# SCH_Carrier-Board_2026-08-28.net
KiCad netlist of a schematic drawn in EasyEDA
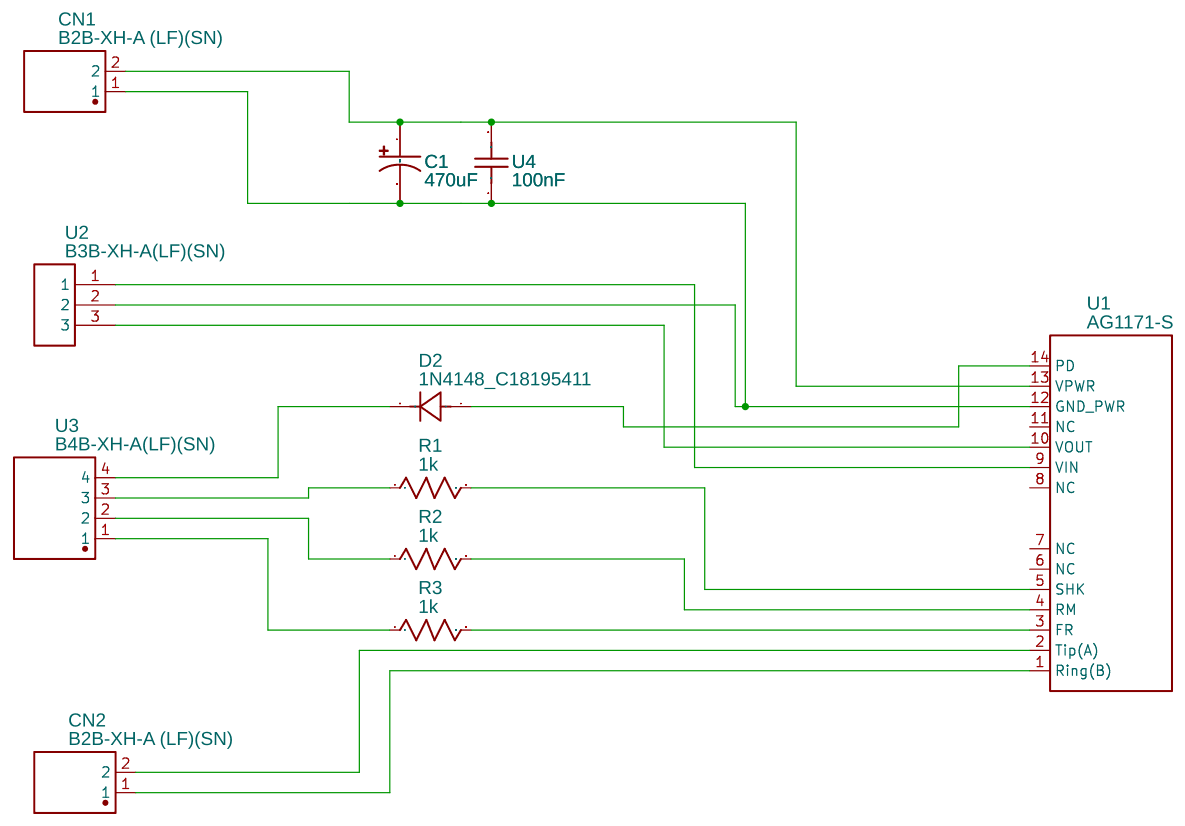
[diagram p0: schematic sheet]

(export (version "E")
  (design (tool "Eeschema 10.0.6"))
  (components
    (comp (ref "C1")
      (value "470uF")
      (fields (field (name "Manufacturer Part") "UPW1C471MPD") (field (name "Manufacturer") "Nichicon(尼吉康)"))
      (libsource (lib "") (part "UPW1C471MPD"))
    )
    (comp (ref "CN1")
      (value "B2B-XH-A (LF)(SN)")
      (fields (field (name "Manufacturer Part") "B2B-XH-A(LF)(SN)") (field (name "Manufacturer") "JST"))
      (libsource (lib "") (part "B2B-XH-A (LF)(SN)"))
    )
    (comp (ref "CN2")
      (value "B2B-XH-A (LF)(SN)")
      (fields (field (name "Manufacturer Part") "B2B-XH-A(LF)(SN)") (field (name "Manufacturer") "JST"))
      (libsource (lib "") (part "B2B-XH-A (LF)(SN)"))
    )
    (comp (ref "D2")
      (value "1N4148_C18195411")
      (fields (field (name "Manufacturer Part") "1N4148") (field (name "Manufacturer") "LJ(朗捷)"))
      (libsource (lib "") (part "1N4148_C18195411"))
    )
    (comp (ref "R1") (value "1k") (libsource (lib "") (part "R_0603_US")))
    (comp (ref "R2") (value "1k") (libsource (lib "") (part "R_0603_US")))
    (comp (ref "R3") (value "1k") (libsource (lib "") (part "R_0603_US")))
    (comp (ref "U1")
      (value "AG1171-S")
      (fields (field (name "Manufacturer") "Silvertel"))
      (libsource (lib "") (part "AG1171-S"))
    )
    (comp (ref "U2")
      (value "B3B-XH-A(LF)(SN)")
      (fields (field (name "Manufacturer") "JST"))
      (libsource (lib "") (part "B3B-XH-A(LF)(SN)"))
    )
    (comp (ref "U3")
      (value "B4B-XH-A(LF)(SN)")
      (fields (field (name "Manufacturer") "JST"))
      (libsource (lib "") (part "B4B-XH-A(LF)(SN)"))
    )
    (comp (ref "U4")
      (value "100nF")
      (fields (field (name "Manufacturer Part") "K104K10X7RF5UH5") (field (name "Manufacturer") "VISHAY(威世)"))
      (libsource (lib "") (part "K104K10X7RF5UH5"))
    )
  )
  (nets
    (net (code "1") (name "Net-(D2-A)") (class "Default")
      (node (ref "D2") (pin "1") (pinfunction "A_1") (pintype "unspecified"))
      (node (ref "U1") (pin "14") (pinfunction "PD_14") (pintype "unspecified"))
    )
    (net (code "2") (name "Net-(D2-C)") (class "Default")
      (node (ref "D2") (pin "2") (pinfunction "C_2") (pintype "unspecified"))
      (node (ref "U3") (pin "4") (pinfunction "4_4") (pintype "unspecified"))
    )
    (net (code "3") (name "Net-(R1-Pad1)") (class "Default")
      (node (ref "R1") (pin "1") (pinfunction "1_1") (pintype "unspecified"))
      (node (ref "U3") (pin "3") (pinfunction "3_3") (pintype "unspecified"))
    )
    (net (code "4") (name "Net-(R2-Pad1)") (class "Default")
      (node (ref "R2") (pin "1") (pinfunction "1_1") (pintype "unspecified"))
      (node (ref "U3") (pin "2") (pinfunction "2_2") (pintype "unspecified"))
    )
    (net (code "5") (name "Net-(R3-Pad1)") (class "Default")
      (node (ref "R3") (pin "1") (pinfunction "1_1") (pintype "unspecified"))
      (node (ref "U3") (pin "1") (pinfunction "1_1") (pintype "unspecified"))
    )
    (net (code "6") (name "Net-(U1-FR)") (class "Default")
      (node (ref "R3") (pin "2") (pinfunction "2_2") (pintype "unspecified"))
      (node (ref "U1") (pin "3") (pinfunction "FR_3") (pintype "unspecified"))
    )
    (net (code "7") (name "Net-(U1-GND_PWR)") (class "Default")
      (node (ref "C1") (pin "2") (pinfunction "2_2") (pintype "unspecified"))
      (node (ref "CN1") (pin "1") (pinfunction "1_1") (pintype "unspecified"))
      (node (ref "U1") (pin "12") (pinfunction "GND_PWR_12") (pintype "unspecified"))
      (node (ref "U2") (pin "2") (pinfunction "2_2") (pintype "unspecified"))
      (node (ref "U4") (pin "1") (pinfunction "1_1") (pintype "unspecified"))
    )
    (net (code "8") (name "Net-(U1-RM)") (class "Default")
      (node (ref "R2") (pin "2") (pinfunction "2_2") (pintype "unspecified"))
      (node (ref "U1") (pin "4") (pinfunction "RM_4") (pintype "unspecified"))
    )
    (net (code "9") (name "Net-(U1-Ring(B))") (class "Default")
      (node (ref "CN2") (pin "1") (pinfunction "1_1") (pintype "unspecified"))
      (node (ref "U1") (pin "1") (pinfunction "Ring(B)_1") (pintype "unspecified"))
    )
    (net (code "10") (name "Net-(U1-SHK)") (class "Default")
      (node (ref "R1") (pin "2") (pinfunction "2_2") (pintype "unspecified"))
      (node (ref "U1") (pin "5") (pinfunction "SHK_5") (pintype "unspecified"))
    )
    (net (code "11") (name "Net-(U1-Tip(A))") (class "Default")
      (node (ref "CN2") (pin "2") (pinfunction "2_2") (pintype "unspecified"))
      (node (ref "U1") (pin "2") (pinfunction "Tip(A)_2") (pintype "unspecified"))
    )
    (net (code "12") (name "Net-(U1-VIN)") (class "Default")
      (node (ref "U1") (pin "9") (pinfunction "VIN_9") (pintype "unspecified"))
      (node (ref "U2") (pin "1") (pinfunction "1_1") (pintype "unspecified"))
    )
    (net (code "13") (name "Net-(U1-VOUT)") (class "Default")
      (node (ref "U1") (pin "10") (pinfunction "VOUT_10") (pintype "unspecified"))
      (node (ref "U2") (pin "3") (pinfunction "3_3") (pintype "unspecified"))
    )
    (net (code "14") (name "Net-(U1-VPWR)") (class "Default")
      (node (ref "C1") (pin "1") (pinfunction "1_1") (pintype "unspecified"))
      (node (ref "CN1") (pin "2") (pinfunction "2_2") (pintype "unspecified"))
      (node (ref "U1") (pin "13") (pinfunction "VPWR_13") (pintype "unspecified"))
      (node (ref "U4") (pin "2") (pinfunction "2_2") (pintype "unspecified"))
    )
    (net (code "15") (name "unconnected-(U1-NC-Pad6)") (class "Default")
      (node (ref "U1") (pin "6") (pinfunction "NC_6") (pintype "unspecified"))
    )
    (net (code "16") (name "unconnected-(U1-NC-Pad7)") (class "Default")
      (node (ref "U1") (pin "7") (pinfunction "NC_7") (pintype "unspecified"))
    )
    (net (code "17") (name "unconnected-(U1-NC-Pad8)") (class "Default")
      (node (ref "U1") (pin "8") (pinfunction "NC_8") (pintype "unspecified"))
    )
    (net (code "18") (name "unconnected-(U1-NC-Pad11)") (class "Default")
      (node (ref "U1") (pin "11") (pinfunction "NC_11") (pintype "unspecified"))
    )
  )
)
